# serra1.net
KiCad netlist of a schematic drawn in EAGLE
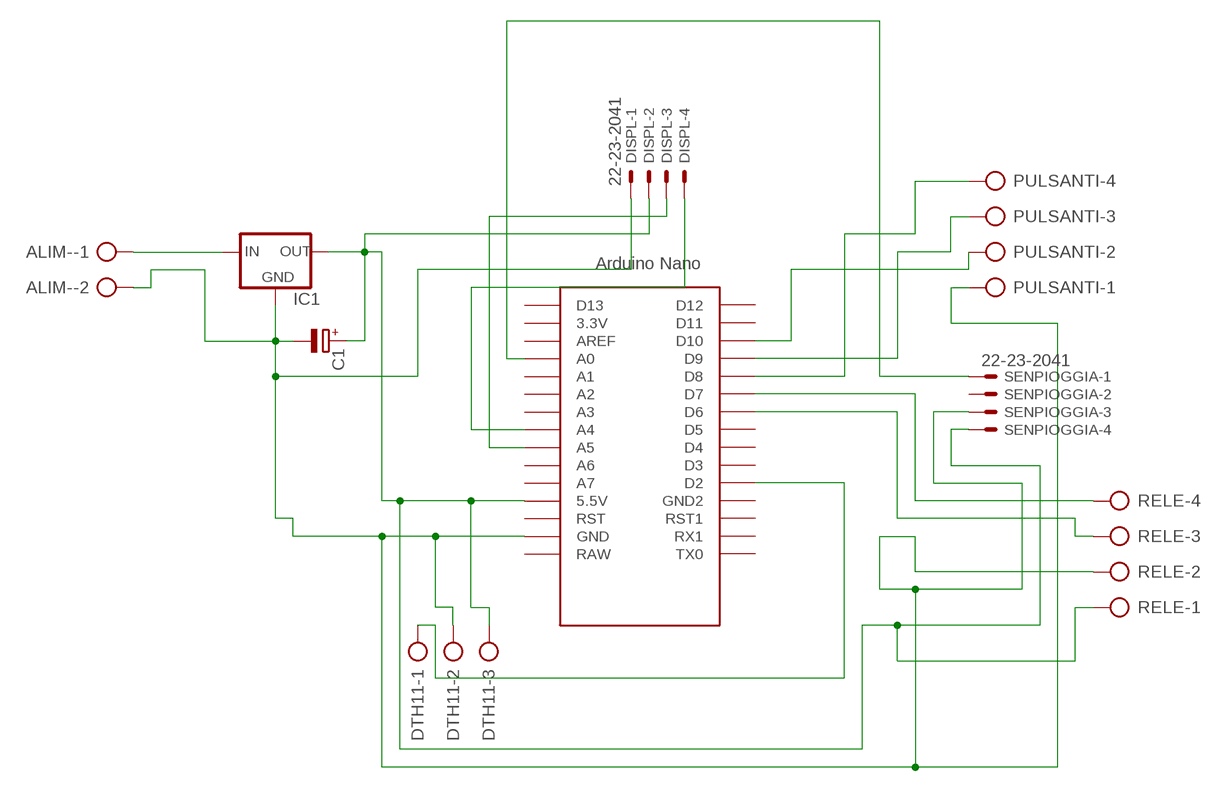
[diagram p0: schematic, sheet 1]

(export (version "E")
  (design (tool "Eeschema 10.0.6"))
  (components
    (comp (ref "ALIM-")
      (value "AK500/2")
      (footprint "eagle-import:AK500_2")
      (libsource (lib "eagle-import") (part "AK500/2"))
    )
    (comp (ref "C1")
      (value "CPOL-EUE5-13")
      (footprint "eagle-import:E5-13")
      (libsource (lib "eagle-import") (part "CPOL-EUE5-13"))
    )
    (comp (ref "DISPL")
      (value "22-23-2041")
      (footprint "eagle-import:22-23-2041")
      (fields (field (name "MF") "MOLEX"))
      (libsource (lib "eagle-import") (part "22-23-2041"))
    )
    (comp (ref "DTH11")
      (value "AK500/3")
      (footprint "eagle-import:AK500_3")
      (libsource (lib "eagle-import") (part "AK500/3"))
    )
    (comp (ref "IC1")
      (value "78XXS")
      (footprint "eagle-import:78XXS")
      (libsource (lib "eagle-import") (part "78XXS"))
    )
    (comp (ref "PULSANTI")
      (value "AK500/4")
      (footprint "eagle-import:AK500_4")
      (libsource (lib "eagle-import") (part "con-ptr500_AK500/4"))
    )
    (comp (ref "RELE")
      (value "AK500/4")
      (footprint "eagle-import:AK500_4")
      (libsource (lib "eagle-import") (part "AK500/4"))
    )
    (comp (ref "SENPIOGGIA")
      (value "22-23-2041")
      (footprint "eagle-import:22-23-2041")
      (fields (field (name "MF") "MOLEX"))
      (libsource (lib "eagle-import") (part "22-23-2041"))
    )
    (comp (ref "U$1")
      (value "NANO")
      (footprint "eagle-import:NANO")
      (libsource (lib "eagle-import") (part "NANO"))
    )
  )
  (nets
    (net (code "1") (name "Net-(ALIM-A-KL)") (class "Default")
      (node (ref "ALIM-") (pin "1") (pinfunction "KL_1") (pintype "passive"))
      (node (ref "IC1") (pin "IN") (pinfunction "IN_IN") (pintype "input"))
    )
    (net (code "2") (name "Net-(ALIM-B-KL)") (class "Default")
      (node (ref "ALIM-") (pin "2") (pinfunction "KL_2") (pintype "passive"))
      (node (ref "C1") (pin "-") (pinfunction "-_-") (pintype "passive"))
      (node (ref "DISPL") (pin "1") (pinfunction "S_1") (pintype "passive"))
      (node (ref "DTH11") (pin "2") (pinfunction "KL_2") (pintype "passive"))
      (node (ref "IC1") (pin "GND") (pinfunction "GND_GND") (pintype "input"))
      (node (ref "PULSANTI") (pin "1") (pinfunction "KL_1") (pintype "passive"))
      (node (ref "RELE") (pin "2") (pinfunction "KL_2") (pintype "passive"))
      (node (ref "SENPIOGGIA") (pin "3") (pinfunction "S_3") (pintype "passive"))
      (node (ref "U$1") (pin "GND") (pinfunction "GND_GND") (pintype "bidirectional"))
    )
    (net (code "3") (name "Net-(DISPLB-S)") (class "Default")
      (node (ref "C1") (pin "+") (pinfunction "+_+") (pintype "passive"))
      (node (ref "DISPL") (pin "2") (pinfunction "S_2") (pintype "passive"))
      (node (ref "DTH11") (pin "3") (pinfunction "KL_3") (pintype "passive"))
      (node (ref "IC1") (pin "OUT") (pinfunction "OUT_OUT") (pintype "passive"))
      (node (ref "RELE") (pin "1") (pinfunction "KL_1") (pintype "passive"))
      (node (ref "SENPIOGGIA") (pin "4") (pinfunction "S_4") (pintype "passive"))
      (node (ref "U$1") (pin "5V") (pinfunction "5.5V_5V") (pintype "bidirectional"))
    )
    (net (code "4") (name "Net-(DISPLC-S)") (class "Default")
      (node (ref "DISPL") (pin "3") (pinfunction "S_3") (pintype "passive"))
      (node (ref "U$1") (pin "A5") (pinfunction "A5_A5") (pintype "bidirectional"))
    )
    (net (code "5") (name "Net-(DISPLD-S)") (class "Default")
      (node (ref "DISPL") (pin "4") (pinfunction "S_4") (pintype "passive"))
      (node (ref "U$1") (pin "A4") (pinfunction "A4_A4") (pintype "bidirectional"))
    )
    (net (code "6") (name "Net-(DTH11A-KL)") (class "Default")
      (node (ref "DTH11") (pin "1") (pinfunction "KL_1") (pintype "passive"))
      (node (ref "U$1") (pin "D2") (pinfunction "D2_D2") (pintype "bidirectional"))
    )
    (net (code "7") (name "Net-(PULSANTIB-KL)") (class "Default")
      (node (ref "PULSANTI") (pin "2") (pinfunction "KL_2") (pintype "passive"))
      (node (ref "U$1") (pin "D10") (pinfunction "D10_D10") (pintype "bidirectional"))
    )
    (net (code "8") (name "Net-(PULSANTIC-KL)") (class "Default")
      (node (ref "PULSANTI") (pin "3") (pinfunction "KL_3") (pintype "passive"))
      (node (ref "U$1") (pin "D9") (pinfunction "D9_D9") (pintype "bidirectional"))
    )
    (net (code "9") (name "Net-(PULSANTID-KL)") (class "Default")
      (node (ref "PULSANTI") (pin "4") (pinfunction "KL_4") (pintype "passive"))
      (node (ref "U$1") (pin "D8") (pinfunction "D8_D8") (pintype "bidirectional"))
    )
    (net (code "10") (name "Net-(RELEC-KL)") (class "Default")
      (node (ref "RELE") (pin "3") (pinfunction "KL_3") (pintype "passive"))
      (node (ref "U$1") (pin "D6") (pinfunction "D6_D6") (pintype "bidirectional"))
    )
    (net (code "11") (name "Net-(RELED-KL)") (class "Default")
      (node (ref "RELE") (pin "4") (pinfunction "KL_4") (pintype "passive"))
      (node (ref "U$1") (pin "D7") (pinfunction "D7_D7") (pintype "bidirectional"))
    )
    (net (code "12") (name "Net-(SENPIOGGIAA-S)") (class "Default")
      (node (ref "SENPIOGGIA") (pin "1") (pinfunction "S_1") (pintype "passive"))
      (node (ref "U$1") (pin "A0") (pinfunction "A0_A0") (pintype "bidirectional"))
    )
    (net (code "13") (name "unconnected-(SENPIOGGIAB-S-Pad2)") (class "Default")
      (node (ref "SENPIOGGIA") (pin "2") (pinfunction "S_2") (pintype "passive"))
    )
    (net (code "14") (name "unconnected-(U$1-GND2-PadGND1)") (class "Default")
      (node (ref "U$1") (pin "GND1") (pinfunction "GND2_GND1") (pintype "bidirectional"))
    )
    (net (code "15") (name "unconnected-(U$1-Pad3.3V)") (class "Default")
      (node (ref "U$1") (pin "3.3V") (pinfunction "3.3V_3.3V") (pintype "bidirectional"))
    )
    (net (code "16") (name "unconnected-(U$1-PadA1)") (class "Default")
      (node (ref "U$1") (pin "A1") (pinfunction "A1_A1") (pintype "bidirectional"))
    )
    (net (code "17") (name "unconnected-(U$1-PadA2)") (class "Default")
      (node (ref "U$1") (pin "A2") (pinfunction "A2_A2") (pintype "bidirectional"))
    )
    (net (code "18") (name "unconnected-(U$1-PadA3)") (class "Default")
      (node (ref "U$1") (pin "A3") (pinfunction "A3_A3") (pintype "bidirectional"))
    )
    (net (code "19") (name "unconnected-(U$1-PadA6)") (class "Default")
      (node (ref "U$1") (pin "A6") (pinfunction "A6_A6") (pintype "bidirectional"))
    )
    (net (code "20") (name "unconnected-(U$1-PadA7)") (class "Default")
      (node (ref "U$1") (pin "A7") (pinfunction "A7_A7") (pintype "bidirectional"))
    )
    (net (code "21") (name "unconnected-(U$1-PadAREF)") (class "Default")
      (node (ref "U$1") (pin "AREF") (pinfunction "AREF_AREF") (pintype "bidirectional"))
    )
    (net (code "22") (name "unconnected-(U$1-PadD3)") (class "Default")
      (node (ref "U$1") (pin "D3") (pinfunction "D3_D3") (pintype "bidirectional"))
    )
    (net (code "23") (name "unconnected-(U$1-PadD4)") (class "Default")
      (node (ref "U$1") (pin "D4") (pinfunction "D4_D4") (pintype "bidirectional"))
    )
    (net (code "24") (name "unconnected-(U$1-PadD5)") (class "Default")
      (node (ref "U$1") (pin "D5") (pinfunction "D5_D5") (pintype "bidirectional"))
    )
    (net (code "25") (name "unconnected-(U$1-PadD11)") (class "Default")
      (node (ref "U$1") (pin "D11") (pinfunction "D11_D11") (pintype "bidirectional"))
    )
    (net (code "26") (name "unconnected-(U$1-PadD12)") (class "Default")
      (node (ref "U$1") (pin "D12") (pinfunction "D12_D12") (pintype "bidirectional"))
    )
    (net (code "27") (name "unconnected-(U$1-PadD13)") (class "Default")
      (node (ref "U$1") (pin "D13") (pinfunction "D13_D13") (pintype "bidirectional"))
    )
    (net (code "28") (name "unconnected-(U$1-PadICSP1)") (class "Default")
      (node (ref "U$1") (pin "ICSP1") (pinfunction "ICSP1_ICSP1") (pintype "bidirectional"))
    )
    (net (code "29") (name "unconnected-(U$1-PadICSP2)") (class "Default")
      (node (ref "U$1") (pin "ICSP2") (pinfunction "ICSP2_ICSP2") (pintype "bidirectional"))
    )
    (net (code "30") (name "unconnected-(U$1-PadICSP3)") (class "Default")
      (node (ref "U$1") (pin "ICSP3") (pinfunction "ICSP3_ICSP3") (pintype "bidirectional"))
    )
    (net (code "31") (name "unconnected-(U$1-PadICSP4)") (class "Default")
      (node (ref "U$1") (pin "ICSP4") (pinfunction "ICSP4_ICSP4") (pintype "bidirectional"))
    )
    (net (code "32") (name "unconnected-(U$1-PadICSP5)") (class "Default")
      (node (ref "U$1") (pin "ICSP5") (pinfunction "ICSP5_ICSP5") (pintype "bidirectional"))
    )
    (net (code "33") (name "unconnected-(U$1-PadICSP6)") (class "Default")
      (node (ref "U$1") (pin "ICSP6") (pinfunction "ICSP6_ICSP6") (pintype "bidirectional"))
    )
    (net (code "34") (name "unconnected-(U$1-PadRAW)") (class "Default")
      (node (ref "U$1") (pin "RAW") (pinfunction "RAW_RAW") (pintype "bidirectional"))
    )
    (net (code "35") (name "unconnected-(U$1-PadRST)") (class "Default")
      (node (ref "U$1") (pin "RST") (pinfunction "RST_RST") (pintype "bidirectional"))
    )
    (net (code "36") (name "unconnected-(U$1-PadRST1)") (class "Default")
      (node (ref "U$1") (pin "RST1") (pinfunction "RST1_RST1") (pintype "bidirectional"))
    )
    (net (code "37") (name "unconnected-(U$1-PadRX1)") (class "Default")
      (node (ref "U$1") (pin "RX1") (pinfunction "RX1_RX1") (pintype "bidirectional"))
    )
    (net (code "38") (name "unconnected-(U$1-PadTX0)") (class "Default")
      (node (ref "U$1") (pin "TX0") (pinfunction "TX0_TX0") (pintype "bidirectional"))
    )
  )
)
